# Dhruvacube_LFR__PCB__Sheet_1_2023-06-07.net
KiCad netlist of a schematic drawn in Altium Designer
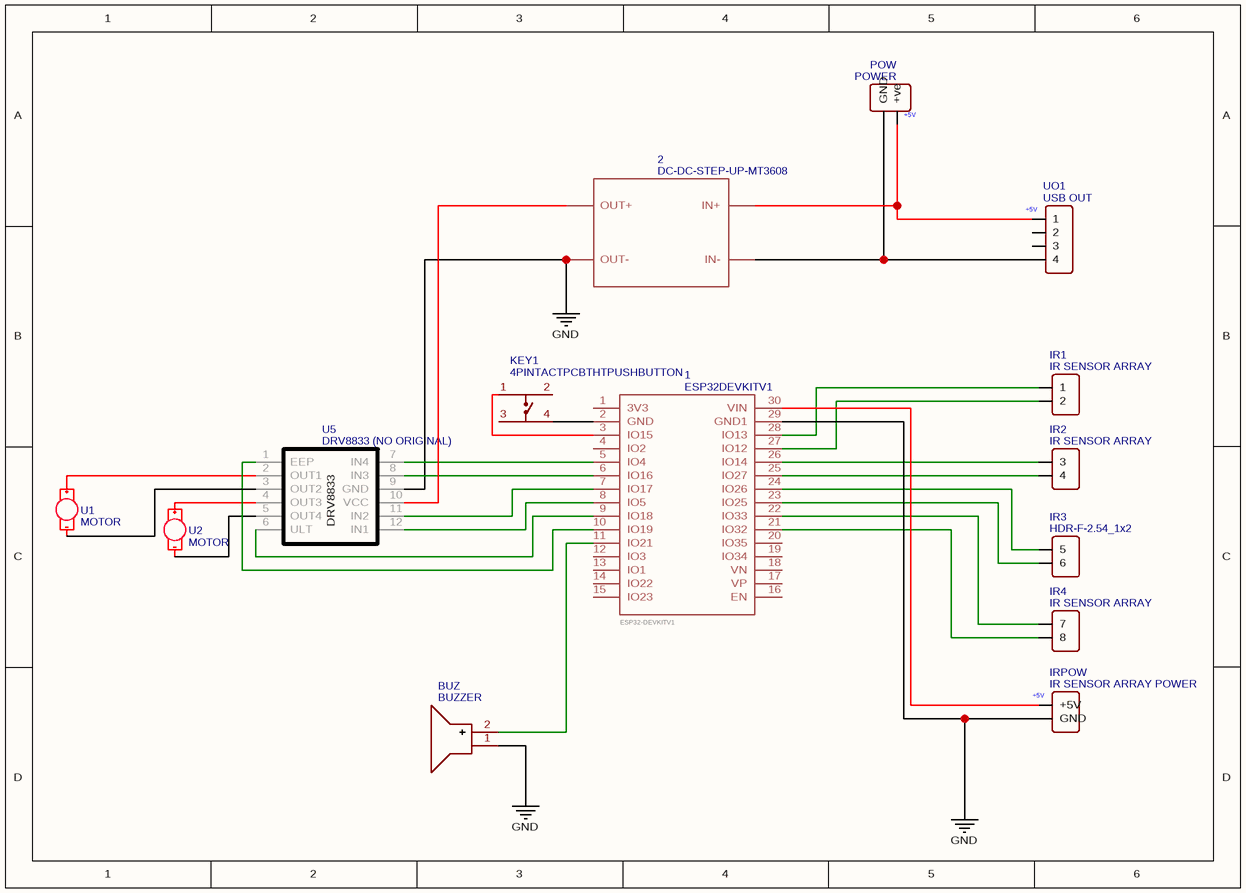
[diagram p0: Dhruvacube_LFR__PCB__Sheet_1_2023-06-07.schdoc]

(export (version "E")
  (design (tool "Eeschema 10.0.6"))
  (components
    (comp (ref "1")
      (value "ESP32DEVKITV1")
      (fields (field (name "CONTRIBUTOR") "Валентин Печенко"))
      (libsource (lib "altium-import") (part "root_3_ESP32DEVKITV1_"))
    )
    (comp (ref "2")
      (value "DC-DC-STEP-UP-MT3608")
      (fields (field (name "CONTRIBUTOR") "arenda1234"))
      (libsource (lib "altium-import") (part "root_0_DC-DC-STEP-UP-MT3608_"))
    )
    (comp (ref "BUZ")
      (value "BUZZER")
      (fields
        (field (name "BOM_SUPPLIER PART") "C9900014030")
        (field (name "BOM_MANUFACTURER PART") "buzzer")
        (field (name "CONTRIBUTOR") "lcsc")
      )
      (libsource (lib "altium-import") (part "root_2_BUZZER_"))
    )
    (comp (ref "IR1")
      (value "IR SENSOR ARRAY")
      (fields (field (name "BOM_SUPPLIER PART") "C49661") (field (name "CONTRIBUTOR") "LCEDA_Lib"))
      (libsource (lib "altium-import") (part "root_0_IR SENSOR ARRAY_"))
    )
    (comp (ref "IR2")
      (value "IR SENSOR ARRAY")
      (fields (field (name "BOM_SUPPLIER PART") "C49661") (field (name "CONTRIBUTOR") "LCEDA_Lib"))
      (libsource (lib "altium-import") (part "root_0_IR SENSOR ARRAY_"))
    )
    (comp (ref "IR3")
      (value "HDR-F-2.54_1x2")
      (fields (field (name "BOM_SUPPLIER PART") "C49661") (field (name "CONTRIBUTOR") "LCEDA_Lib"))
      (libsource (lib "altium-import") (part "root_0_HDR-F-2.54_1x2_"))
    )
    (comp (ref "IR4")
      (value "IR SENSOR ARRAY")
      (fields (field (name "BOM_SUPPLIER PART") "C49661") (field (name "CONTRIBUTOR") "LCEDA_Lib"))
      (libsource (lib "altium-import") (part "root_0_IR SENSOR ARRAY_"))
    )
    (comp (ref "IRPOW")
      (value "IR SENSOR ARRAY POWER")
      (fields (field (name "BOM_SUPPLIER PART") "C49661") (field (name "CONTRIBUTOR") "LCEDA_Lib"))
      (libsource (lib "altium-import") (part "root_0_IR SENSOR ARRAY POWER_"))
    )
    (comp (ref "KEY1")
      (value "4PINTACTPCBTHTPUSHBUTTON")
      (fields
        (field (name "BOM_SUPPLIER PART") "C9900003768")
        (field (name "BOM_MANUFACTURER PART") "4pinTACTPCBTHTPushButton")
        (field (name "CONTRIBUTOR") "LCSC")
      )
      (libsource (lib "altium-import") (part "root_0_4PINTACTPCBTHTPUSHBUTTON_"))
    )
    (comp (ref "POW")
      (value "POWER")
      (fields (field (name "BOM_SUPPLIER PART") "C49661") (field (name "CONTRIBUTOR") "LCEDA_Lib"))
      (libsource (lib "altium-import") (part "root_1_POWER_"))
    )
    (comp (ref "U1")
      (value "MOTOR")
      (fields (field (name "CONTRIBUTOR") "Tuấn Phạm"))
      (libsource (lib "altium-import") (part "root_0_MOTOR_"))
    )
    (comp (ref "U2")
      (value "MOTOR")
      (fields (field (name "CONTRIBUTOR") "Tuấn Phạm"))
      (libsource (lib "altium-import") (part "root_0_MOTOR_"))
    )
    (comp (ref "U5")
      (value "DRV8833 (NO ORIGINAL)")
      (fields (field (name "CONTRIBUTOR") "PiterSantaCruz"))
      (libsource (lib "altium-import") (part "root_0_DRV8833 (NO ORIGINAL)_"))
    )
    (comp (ref "UO1")
      (value "USB OUT")
      (fields (field (name "BOM_SUPPLIER PART") "C225501") (field (name "CONTRIBUTOR") "LCEDA_Lib"))
      (libsource (lib "altium-import") (part "root_0_USB OUT_"))
    )
  )
  (nets
    (net (code "1") (name "GND") (class "Default")
      (node (ref "1") (pin "29") (pinfunction "GND1_29") (pintype "passive"))
      (node (ref "2") (pin "OUT-") (pinfunction "OUT-_OUT-") (pintype "passive"))
      (node (ref "BUZ") (pin "1") (pinfunction "-_1") (pintype "passive"))
      (node (ref "IRPOW") (pin "2") (pinfunction "GND_2") (pintype "passive"))
      (node (ref "U5") (pin "9") (pinfunction "GND_9") (pintype "passive"))
    )
    (net (code "2") (name "Net-(1-GND)") (class "Default")
      (node (ref "1") (pin "2") (pinfunction "GND_2") (pintype "passive"))
      (node (ref "KEY1") (pin "4") (pinfunction "4_4") (pintype "passive"))
    )
    (net (code "3") (name "Net-(1-IO4)") (class "Default")
      (node (ref "1") (pin "5") (pinfunction "IO4_5") (pintype "passive"))
      (node (ref "U5") (pin "7") (pinfunction "IN4_7") (pintype "passive"))
    )
    (net (code "4") (name "Net-(1-IO5)") (class "Default")
      (node (ref "1") (pin "8") (pinfunction "IO5_8") (pintype "passive"))
      (node (ref "U5") (pin "12") (pinfunction "IN1_12") (pintype "passive"))
    )
    (net (code "5") (name "Net-(1-IO12)") (class "Default")
      (node (ref "1") (pin "27") (pinfunction "IO12_27") (pintype "passive"))
      (node (ref "IR1") (pin "2") (pinfunction "2_2") (pintype "passive"))
    )
    (net (code "6") (name "Net-(1-IO13)") (class "Default")
      (node (ref "1") (pin "28") (pinfunction "IO13_28") (pintype "passive"))
      (node (ref "IR1") (pin "1") (pinfunction "1_1") (pintype "passive"))
    )
    (net (code "7") (name "Net-(1-IO14)") (class "Default")
      (node (ref "1") (pin "26") (pinfunction "IO14_26") (pintype "passive"))
      (node (ref "IR2") (pin "1") (pinfunction "1_1") (pintype "passive"))
    )
    (net (code "8") (name "Net-(1-IO15)") (class "Default")
      (node (ref "1") (pin "3") (pinfunction "IO15_3") (pintype "passive"))
      (node (ref "KEY1") (pin "1") (pinfunction "1_1") (pintype "passive"))
    )
    (net (code "9") (name "Net-(1-IO16)") (class "Default")
      (node (ref "1") (pin "6") (pinfunction "IO16_6") (pintype "passive"))
      (node (ref "U5") (pin "8") (pinfunction "IN3_8") (pintype "passive"))
    )
    (net (code "10") (name "Net-(1-IO17)") (class "Default")
      (node (ref "1") (pin "7") (pinfunction "IO17_7") (pintype "passive"))
      (node (ref "U5") (pin "11") (pinfunction "IN2_11") (pintype "passive"))
    )
    (net (code "11") (name "Net-(1-IO18)") (class "Default")
      (node (ref "1") (pin "9") (pinfunction "IO18_9") (pintype "passive"))
      (node (ref "U5") (pin "6") (pinfunction "ULT_6") (pintype "passive"))
    )
    (net (code "12") (name "Net-(1-IO19)") (class "Default")
      (node (ref "1") (pin "10") (pinfunction "IO19_10") (pintype "passive"))
      (node (ref "U5") (pin "1") (pinfunction "EEP_1") (pintype "passive"))
    )
    (net (code "13") (name "Net-(1-IO21)") (class "Default")
      (node (ref "1") (pin "11") (pinfunction "IO21_11") (pintype "passive"))
      (node (ref "BUZ") (pin "2") (pinfunction "+_2") (pintype "passive"))
    )
    (net (code "14") (name "Net-(1-IO25)") (class "Default")
      (node (ref "1") (pin "23") (pinfunction "IO25_23") (pintype "passive"))
      (node (ref "IR3") (pin "2") (pinfunction "6_2") (pintype "passive"))
    )
    (net (code "15") (name "Net-(1-IO26)") (class "Default")
      (node (ref "1") (pin "24") (pinfunction "IO26_24") (pintype "passive"))
      (node (ref "IR3") (pin "1") (pinfunction "5_1") (pintype "passive"))
    )
    (net (code "16") (name "Net-(1-IO27)") (class "Default")
      (node (ref "1") (pin "25") (pinfunction "IO27_25") (pintype "passive"))
      (node (ref "IR2") (pin "2") (pinfunction "2_2") (pintype "passive"))
    )
    (net (code "17") (name "Net-(1-IO32)") (class "Default")
      (node (ref "1") (pin "21") (pinfunction "IO32_21") (pintype "passive"))
      (node (ref "IR4") (pin "2") (pinfunction "2_2") (pintype "passive"))
    )
    (net (code "18") (name "Net-(1-IO33)") (class "Default")
      (node (ref "1") (pin "22") (pinfunction "IO33_22") (pintype "passive"))
      (node (ref "IR4") (pin "1") (pinfunction "1_1") (pintype "passive"))
    )
    (net (code "19") (name "Net-(1-VIN)") (class "Default")
      (node (ref "1") (pin "30") (pinfunction "VIN_30") (pintype "passive"))
      (node (ref "IRPOW") (pin "1") (pinfunction "+5V_1") (pintype "passive"))
    )
    (net (code "20") (name "Net-(POW-+ve)") (class "Default")
      (node (ref "2") (pin "IN+") (pinfunction "IN+_IN+") (pintype "passive"))
      (node (ref "POW") (pin "1") (pinfunction "+ve_1") (pintype "passive"))
      (node (ref "UO1") (pin "1") (pinfunction "1_1") (pintype "passive"))
    )
    (net (code "21") (name "Net-(POW-GND)") (class "Default")
      (node (ref "2") (pin "IN-") (pinfunction "IN-_IN-") (pintype "passive"))
      (node (ref "POW") (pin "2") (pinfunction "GND_2") (pintype "passive"))
      (node (ref "UO1") (pin "4") (pinfunction "4_4") (pintype "passive"))
    )
    (net (code "22") (name "Net-(U5-OUT1)") (class "Default")
      (node (ref "U1") (pin "+") (pinfunction "+_+") (pintype "passive"))
      (node (ref "U5") (pin "2") (pinfunction "OUT1_2") (pintype "passive"))
    )
    (net (code "23") (name "Net-(U5-OUT2)") (class "Default")
      (node (ref "U1") (pin "-") (pinfunction "-_-") (pintype "passive"))
      (node (ref "U5") (pin "3") (pinfunction "OUT2_3") (pintype "passive"))
    )
    (net (code "24") (name "Net-(U5-OUT3)") (class "Default")
      (node (ref "U2") (pin "+") (pinfunction "+_+") (pintype "passive"))
      (node (ref "U5") (pin "4") (pinfunction "OUT3_4") (pintype "passive"))
    )
    (net (code "25") (name "Net-(U5-OUT4)") (class "Default")
      (node (ref "U2") (pin "-") (pinfunction "-_-") (pintype "passive"))
      (node (ref "U5") (pin "5") (pinfunction "OUT4_5") (pintype "passive"))
    )
    (net (code "26") (name "Net-(U5-VCC)") (class "Default")
      (node (ref "2") (pin "OUT+") (pinfunction "OUT+_OUT+") (pintype "passive"))
      (node (ref "U5") (pin "10") (pinfunction "VCC_10") (pintype "passive"))
    )
    (net (code "27") (name "unconnected-(1-3V3-Pad1)") (class "Default")
      (node (ref "1") (pin "1") (pinfunction "3V3_1") (pintype "passive"))
    )
    (net (code "28") (name "unconnected-(1-EN-Pad16)") (class "Default")
      (node (ref "1") (pin "16") (pinfunction "EN_16") (pintype "passive"))
    )
    (net (code "29") (name "unconnected-(1-IO1-Pad13)") (class "Default")
      (node (ref "1") (pin "13") (pinfunction "IO1_13") (pintype "passive"))
    )
    (net (code "30") (name "unconnected-(1-IO2-Pad4)") (class "Default")
      (node (ref "1") (pin "4") (pinfunction "IO2_4") (pintype "passive"))
    )
    (net (code "31") (name "unconnected-(1-IO3-Pad12)") (class "Default")
      (node (ref "1") (pin "12") (pinfunction "IO3_12") (pintype "passive"))
    )
    (net (code "32") (name "unconnected-(1-IO22-Pad14)") (class "Default")
      (node (ref "1") (pin "14") (pinfunction "IO22_14") (pintype "passive"))
    )
    (net (code "33") (name "unconnected-(1-IO23-Pad15)") (class "Default")
      (node (ref "1") (pin "15") (pinfunction "IO23_15") (pintype "passive"))
    )
    (net (code "34") (name "unconnected-(1-IO34-Pad19)") (class "Default")
      (node (ref "1") (pin "19") (pinfunction "IO34_19") (pintype "passive"))
    )
    (net (code "35") (name "unconnected-(1-IO35-Pad20)") (class "Default")
      (node (ref "1") (pin "20") (pinfunction "IO35_20") (pintype "passive"))
    )
    (net (code "36") (name "unconnected-(1-VN-Pad18)") (class "Default")
      (node (ref "1") (pin "18") (pinfunction "VN_18") (pintype "passive"))
    )
    (net (code "37") (name "unconnected-(1-VP-Pad17)") (class "Default")
      (node (ref "1") (pin "17") (pinfunction "VP_17") (pintype "passive"))
    )
    (net (code "38") (name "unconnected-(KEY1-Pad2)") (class "Default")
      (node (ref "KEY1") (pin "2") (pinfunction "2_2") (pintype "passive"))
    )
    (net (code "39") (name "unconnected-(KEY1-Pad3)") (class "Default")
      (node (ref "KEY1") (pin "3") (pinfunction "3_3") (pintype "passive"))
    )
    (net (code "40") (name "unconnected-(UO1-Pad2)") (class "Default")
      (node (ref "UO1") (pin "2") (pinfunction "2_2") (pintype "passive"))
    )
    (net (code "41") (name "unconnected-(UO1-Pad3)") (class "Default")
      (node (ref "UO1") (pin "3") (pinfunction "3_3") (pintype "passive"))
    )
  )
)
